# Instrumentation_Amp.net
KiCad netlist of a schematic drawn in Altium Designer
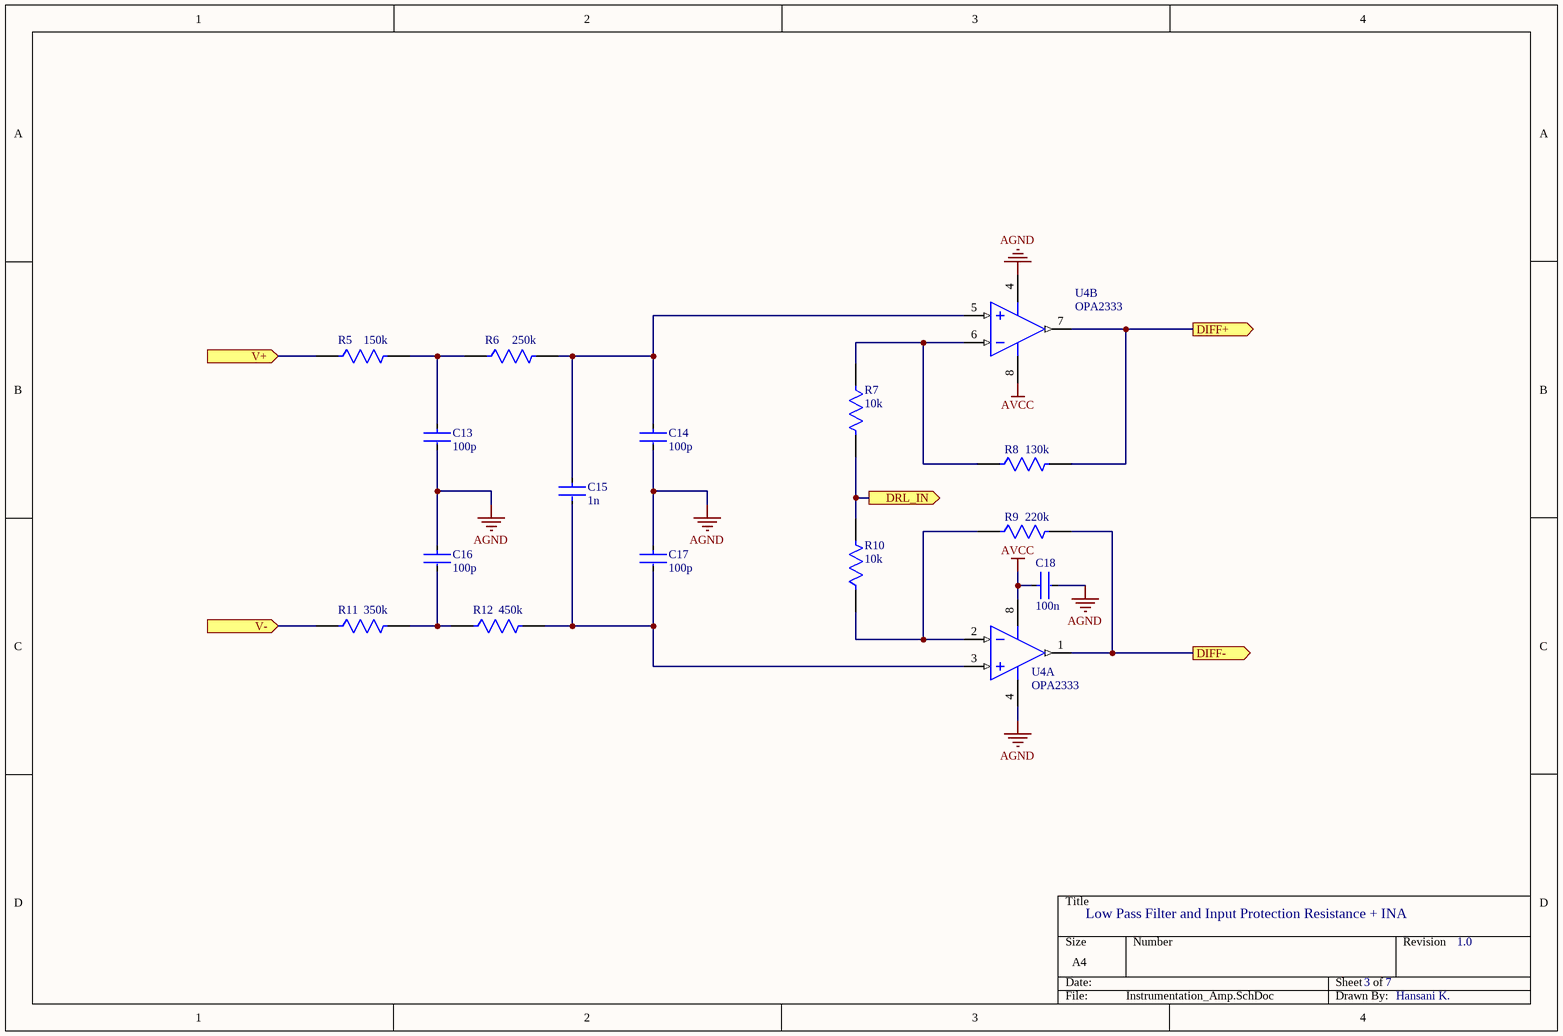
[diagram p0: Instrumentation_Amp.SchDoc]

(export (version "E")
  (design (tool "Eeschema 10.0.6"))
  (components
    (comp (ref "C13")
      (value "100p")
      (footprint "FP-CC0805-0_1-0_7-IPC_A")
      (description "CAP CER 100PF 50V C0G/NPO 0805")
      (fields (field (name "VOLTAGE") "50V") (field (name "TOLERANCE") "5%"))
      (libsource (lib "Altium Content Vault") (part "02cd4be3c70576c341d710602a673aa"))
    )
    (comp (ref "C14")
      (value "100p")
      (footprint "FP-CC0805-0_1-0_7-IPC_A")
      (description "CAP CER 100PF 50V C0G/NPO 0805")
      (fields (field (name "VOLTAGE") "50V") (field (name "TOLERANCE") "5%"))
      (libsource (lib "Altium Content Vault") (part "02cd4be3c70576c341d710602a673aa"))
    )
    (comp (ref "C15")
      (value "1n")
      (footprint "PCBComponent_1")
      (fields
        (field (name "MANUFACTURER") "Yageo Group")
        (field (name "MANUFACTURER PART NUMBER") "CS0805KRX7RBBB102")
        (field (name "TOLERANCE") "10%")
      )
      (libsource (lib "Schlib1") (part "CS0805KRX7RBBB102"))
    )
    (comp (ref "C16")
      (value "100p")
      (footprint "FP-CC0805-0_1-0_7-IPC_A")
      (description "CAP CER 100PF 50V C0G/NPO 0805")
      (fields (field (name "VOLTAGE") "50V") (field (name "TOLERANCE") "5%"))
      (libsource (lib "Altium Content Vault") (part "02cd4be3c70576c341d710602a673aa"))
    )
    (comp (ref "C17")
      (value "100p")
      (footprint "FP-CC0805-0_1-0_7-IPC_A")
      (description "CAP CER 100PF 50V C0G/NPO 0805")
      (fields (field (name "VOLTAGE") "50V") (field (name "TOLERANCE") "5%"))
      (libsource (lib "Altium Content Vault") (part "02cd4be3c70576c341d710602a673aa"))
    )
    (comp (ref "C18")
      (value "100n")
      (footprint "FP-GRM155-0_05-MFG")
      (description "Chip Multilayer Ceramic Capacitors for General Purpose, 0402, 0.10uF, B, 10%, 20%, 50V")
      (libsource (lib "Altium Content Vault") (part "02cd4be3c70576c341d710602a673aa"))
    )
    (comp (ref "R5")
      (value "150k")
      (footprint "PCBComponent_1")
      (description "ERJ Thick Film Chip Resistor 0805 350K Ohm 5% 0.125 W 2-Pin Surface Mount Punched Carrier T/R")
      (fields
        (field (name "MANUFACTURER") "Panasonic")
        (field (name "MANUFACTURER PART NUMBER") "ERJ-6GEYJ354V")
      )
      (libsource (lib "Schlib1") (part "ERJ-6GEYJ354V"))
    )
    (comp (ref "R6")
      (value "250k")
      (footprint "PCBComponent_1")
      (description "RNCF Precision Thin Film Chip Resistor 0805 Size 250K Ohm 0.1% 0.25 W 25 ppm/°C 2-Pin SMD T/R")
      (fields
        (field (name "MANUFACTURER") "Stackpole Electronics")
        (field (name "MANUFACTURER PART NUMBER") "RNCF0805BTE250K")
      )
      (libsource (lib "Schlib1") (part "RNCF0805BTE250K"))
    )
    (comp (ref "R7")
      (value "10k")
      (footprint "FP-AT0805-MFG")
      (description "Thin Film Chip Resistors Automotive Grade 10kΩ 0.5% 50ppm/°C 0805")
      (fields (field (name "TOLERANCE") "0.5%"))
      (libsource (lib "Altium Content Vault") (part "1029c3af85768c4190bb7ad29bc67b5"))
    )
    (comp (ref "R8")
      (value "130k")
      (footprint "FP-RN732A-MFG")
      (description "SMD Chip Resistor, Thin Film, 130KΩ, 100 V, 0805 [2012 Metric], 100 mW, 0.1%, RN73 Series")
      (fields (field (name "MANUFACTURER") "TE Connectivity") (field (name "TOLERANCE") "0.1%"))
      (libsource (lib "Altium Content Vault") (part "1029c3af85768c4190bb7ad29bc67b5"))
    )
    (comp (ref "R9")
      (value "220k")
      (footprint "FP-CRCW0805-e3-IPC_B")
      (description "RES Thick Film, 220kΩ, 1%, 0.125W, 100ppm/°C, 0805")
      (fields (field (name "TOLERANCE") "1%"))
      (libsource (lib "Altium Content Vault") (part "1029c3af85768c4190bb7ad29bc67b5"))
    )
    (comp (ref "R10")
      (value "10k")
      (footprint "FP-AT0805-MFG")
      (description "Thin Film Chip Resistors Automotive Grade 10kΩ 0.5% 50ppm/°C 0805")
      (fields (field (name "TOLERANCE") "0.5%"))
      (libsource (lib "Altium Content Vault") (part "1029c3af85768c4190bb7ad29bc67b5"))
    )
    (comp (ref "R11")
      (value "350k")
      (footprint "PCBComponent_1")
      (description "ERJ Thick Film Chip Resistor 0805 350K Ohm 5% 0.125 W 2-Pin Surface Mount Punched Carrier T/R")
      (fields
        (field (name "MANUFACTURER") "Panasonic")
        (field (name "MANUFACTURER PART NUMBER") "ERJ-6GEYJ354V")
      )
      (libsource (lib "Schlib1") (part "ERJ-6GEYJ354V"))
    )
    (comp (ref "R12")
      (value "450k")
      (footprint "PCBComponent_1")
      (description "Rmk 55N 450K 0, 1% E /Waffle Pack ¦Vishay RMK55N450KB")
      (fields (field (name "MANUFACTURER") "Vishay") (field (name "MANUFACTURER PART NUMBER") "RMK55N450KB"))
      (libsource (lib "Schlib1") (part "RMK55N450KB"))
    )
    (comp (ref "U4")
      (value "OPA2333")
      (footprint "DGK0008A_M")
      (fields (field (name "MANUFACTURER") "Texas Instruments") (field (name "PARTNUMBER") "OPA2333AIDGKR"))
      (libsource (lib "Altium Content Vault") (part "TI-OPA-8_2"))
    )
  )
  (nets
    (net (code "1") (name "/DIFF+") (class "Default")
      (node (ref "R8") (pin "2") (pinfunction "2_2") (pintype "passive"))
      (node (ref "U4") (pin "7") (pinfunction "OUT_B_7") (pintype "output"))
    )
    (net (code "2") (name "/DIFF-") (class "Default")
      (node (ref "R9") (pin "2") (pinfunction "2_2") (pintype "passive"))
      (node (ref "U4") (pin "1") (pinfunction "OUT_A_1") (pintype "output"))
    )
    (net (code "3") (name "/DRL_IN") (class "Default")
      (node (ref "R10") (pin "2") (pinfunction "2_2") (pintype "passive"))
      (node (ref "R7") (pin "2") (pinfunction "2_2") (pintype "passive"))
    )
    (net (code "4") (name "/V+") (class "Default")
      (node (ref "R5") (pin "1") (pinfunction "1_1") (pintype "passive"))
    )
    (net (code "5") (name "/V-") (class "Default")
      (node (ref "R11") (pin "1") (pinfunction "1_1") (pintype "passive"))
    )
    (net (code "6") (name "AGND") (class "Default")
      (node (ref "C13") (pin "2") (pinfunction "2_2") (pintype "passive"))
      (node (ref "C14") (pin "2") (pinfunction "2_2") (pintype "passive"))
      (node (ref "C16") (pin "1") (pinfunction "1_1") (pintype "passive"))
      (node (ref "C17") (pin "1") (pinfunction "1_1") (pintype "passive"))
      (node (ref "C18") (pin "2") (pinfunction "2_2") (pintype "passive"))
      (node (ref "U4") (pin "4") (pinfunction "V-_4") (pintype "power_in"))
    )
    (net (code "7") (name "AVCC") (class "Default")
      (node (ref "C18") (pin "1") (pinfunction "1_1") (pintype "passive"))
      (node (ref "U4") (pin "8") (pinfunction "V+_8") (pintype "power_in"))
    )
    (net (code "8") (name "Net-(C13-Pad1)") (class "Default")
      (node (ref "C13") (pin "1") (pinfunction "1_1") (pintype "passive"))
      (node (ref "R5") (pin "2") (pinfunction "2_2") (pintype "passive"))
      (node (ref "R6") (pin "1") (pinfunction "1_1") (pintype "passive"))
    )
    (net (code "9") (name "Net-(C16-Pad2)") (class "Default")
      (node (ref "C16") (pin "2") (pinfunction "2_2") (pintype "passive"))
      (node (ref "R11") (pin "2") (pinfunction "2_2") (pintype "passive"))
      (node (ref "R12") (pin "1") (pinfunction "1_1") (pintype "passive"))
    )
    (net (code "10") (name "Net-(U4A-IN_A+)") (class "Default")
      (node (ref "C15") (pin "2") (pinfunction "2_2") (pintype "passive"))
      (node (ref "C17") (pin "2") (pinfunction "2_2") (pintype "passive"))
      (node (ref "R12") (pin "2") (pinfunction "2_2") (pintype "passive"))
      (node (ref "U4") (pin "3") (pinfunction "IN_A+_3") (pintype "input"))
    )
    (net (code "11") (name "Net-(U4A-IN_A-)") (class "Default")
      (node (ref "R10") (pin "1") (pinfunction "1_1") (pintype "passive"))
      (node (ref "R9") (pin "1") (pinfunction "1_1") (pintype "passive"))
      (node (ref "U4") (pin "2") (pinfunction "IN_A-_2") (pintype "input"))
    )
    (net (code "12") (name "Net-(U4B-IN_B+)") (class "Default")
      (node (ref "C14") (pin "1") (pinfunction "1_1") (pintype "passive"))
      (node (ref "C15") (pin "1") (pinfunction "1_1") (pintype "passive"))
      (node (ref "R6") (pin "2") (pinfunction "2_2") (pintype "passive"))
      (node (ref "U4") (pin "5") (pinfunction "IN_B+_5") (pintype "input"))
    )
    (net (code "13") (name "Net-(U4B-IN_B-)") (class "Default")
      (node (ref "R7") (pin "1") (pinfunction "1_1") (pintype "passive"))
      (node (ref "R8") (pin "1") (pinfunction "1_1") (pintype "passive"))
      (node (ref "U4") (pin "6") (pinfunction "IN_B-_6") (pintype "input"))
    )
  )
)
